# bromsbank.net
KiCad netlist of a schematic drawn in EAGLE
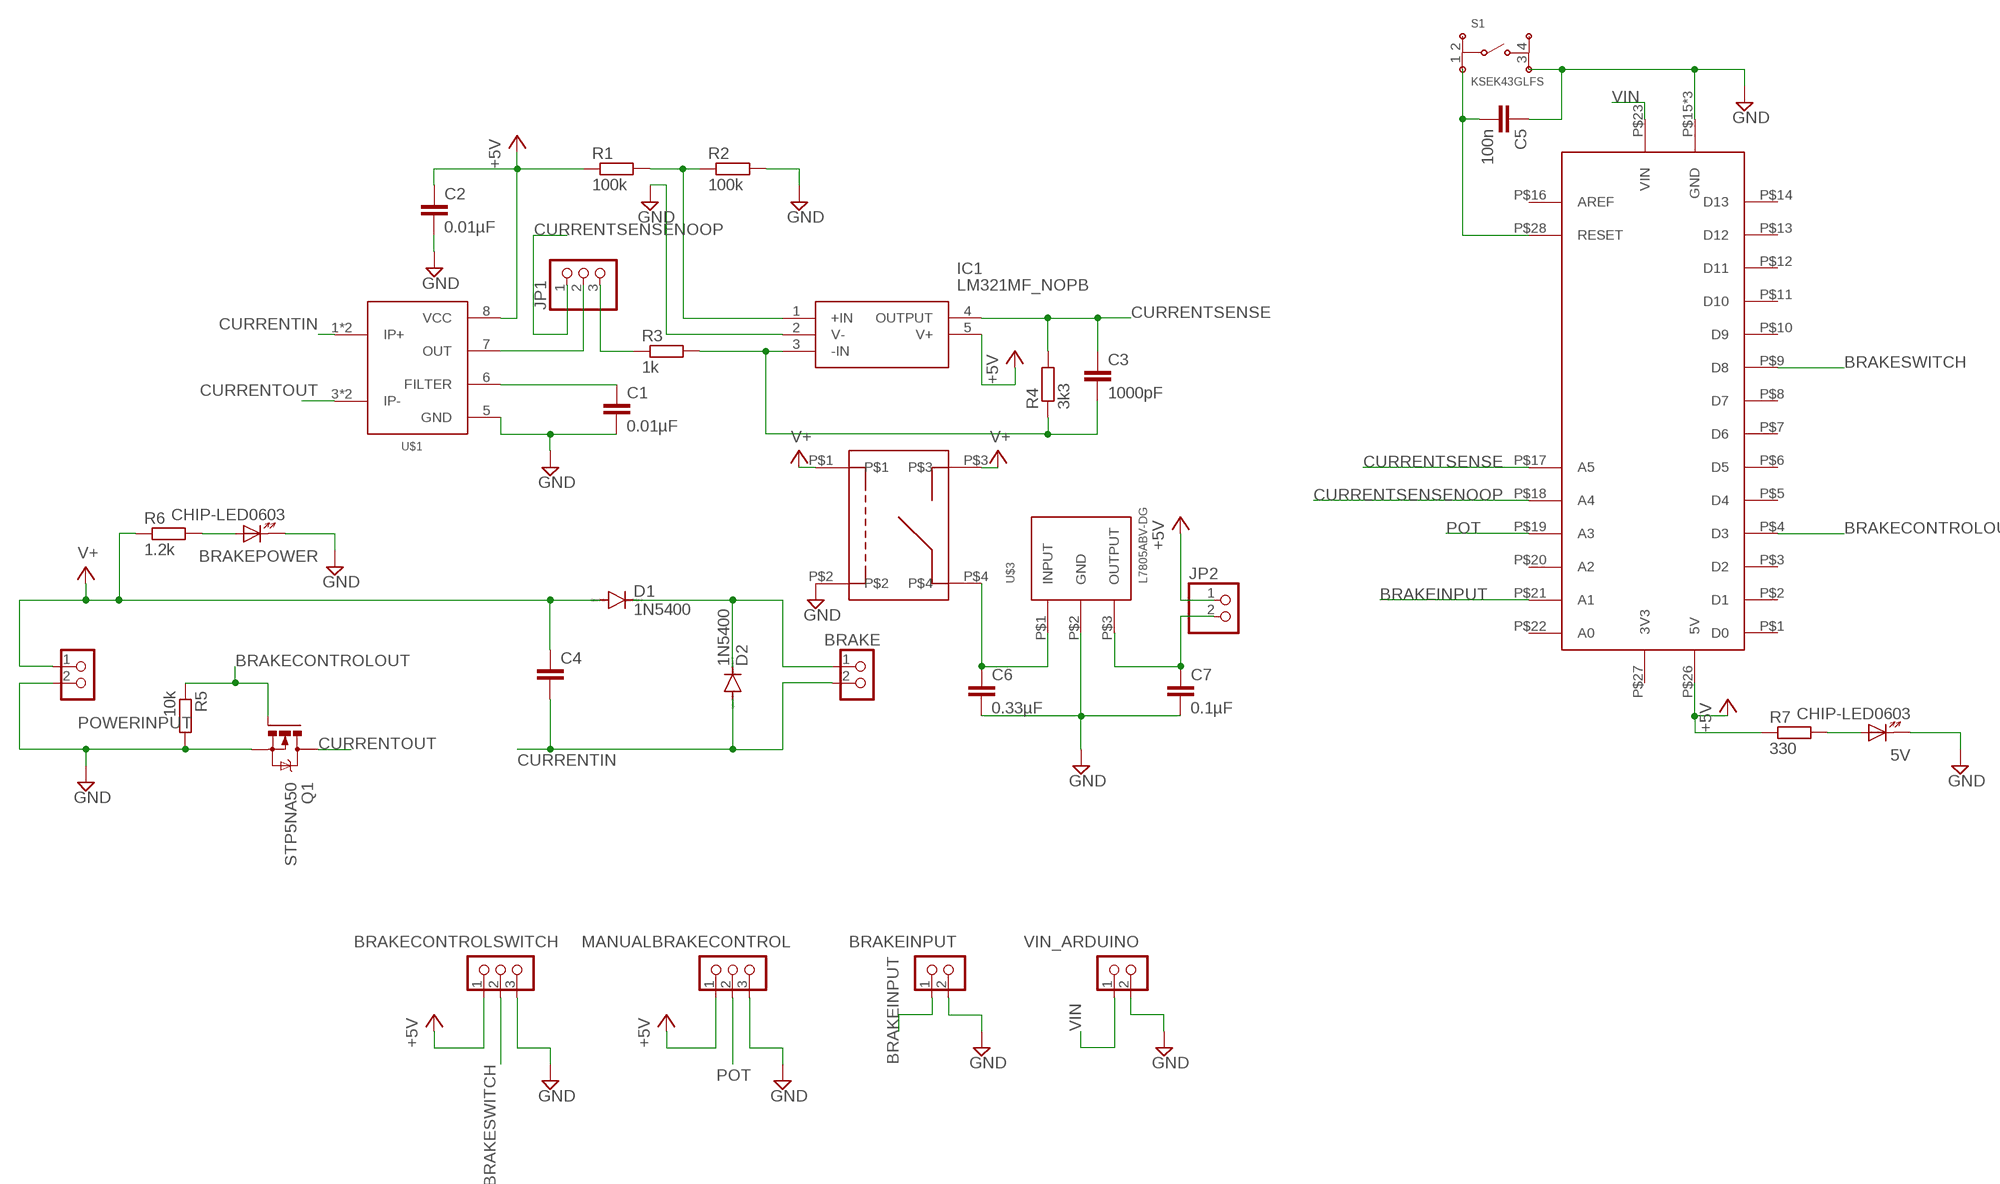
[diagram p0: schematic, sheet 1]

(export (version "E")
  (design (tool "Eeschema 10.0.6"))
  (components
    (comp (ref "5V")
      (value "CHIP-LED0603")
      (footprint "eagle-import:CHIP-LED0603")
      (libsource (lib "eagle-import") (part "CHIP-LED0603"))
    )
    (comp (ref "BRAKE")
      (value "EH_B2B-EH")
      (footprint "eagle-import:B2B-EH")
      (libsource (lib "eagle-import") (part "EH_B2B-EH"))
    )
    (comp (ref "BRAKECONTROLSWITCH")
      (value "EH_B3B-EH")
      (footprint "eagle-import:B3B-EH")
      (libsource (lib "eagle-import") (part "EH_B3B-EH"))
    )
    (comp (ref "BRAKEINPUT")
      (value "EH_B2B-EH")
      (footprint "eagle-import:B2B-EH")
      (libsource (lib "eagle-import") (part "EH_B2B-EH"))
    )
    (comp (ref "BRAKEPOWER")
      (value "CHIP-LED0603")
      (footprint "eagle-import:CHIP-LED0603")
      (libsource (lib "eagle-import") (part "CHIP-LED0603"))
    )
    (comp (ref "C1")
      (value "0.01µF")
      (footprint "eagle-import:C0603")
      (fields (field (name "SPICEPREFIX") "C"))
      (libsource (lib "eagle-import") (part "C0603"))
    )
    (comp (ref "C2")
      (value "0.01µF")
      (footprint "eagle-import:C0603")
      (libsource (lib "eagle-import") (part "C0603"))
    )
    (comp (ref "C3")
      (value "1000pF")
      (footprint "eagle-import:C0603")
      (libsource (lib "eagle-import") (part "C0603"))
    )
    (comp (ref "C4")
      (value "C-EU075-063X106")
      (footprint "eagle-import:C075-063X106")
      (libsource (lib "eagle-import") (part "C-EU075-063X106"))
    )
    (comp (ref "C5")
      (value "100n")
      (footprint "eagle-import:C0603")
      (libsource (lib "eagle-import") (part "C0603"))
    )
    (comp (ref "C6")
      (value "0.33µF")
      (footprint "eagle-import:C0603")
      (fields (field (name "SPICEPREFIX") "C"))
      (libsource (lib "eagle-import") (part "C0603"))
    )
    (comp (ref "C7")
      (value "0.1µF")
      (footprint "eagle-import:C0603")
      (fields (field (name "SPICEPREFIX") "C"))
      (libsource (lib "eagle-import") (part "C0603"))
    )
    (comp (ref "D1")
      (value "1N5400")
      (footprint "eagle-import:DO201-15")
      (libsource (lib "eagle-import") (part "1N5400"))
    )
    (comp (ref "D2")
      (value "1N5400")
      (footprint "eagle-import:DO201-15")
      (libsource (lib "eagle-import") (part "1N5400"))
    )
    (comp (ref "IC1")
      (value "LM321MF_NOPB")
      (footprint "eagle-import:SOT95P280X145-5N")
      (fields
        (field (name "MANUFACTURER_PART_NUMBER") "LM321MF/NOPB")
        (field (name "MOUSER_PART_NUMBER") "926-LM321MF/NOPB")
      )
      (libsource (lib "eagle-import") (part "LM321MF_NOPB"))
    )
    (comp (ref "JP1")
      (value "PINHD-1X3")
      (footprint "eagle-import:1X03")
      (libsource (lib "eagle-import") (part "PINHD-1X3"))
    )
    (comp (ref "JP2")
      (value "PINHD-1X2")
      (footprint "eagle-import:1X02")
      (libsource (lib "eagle-import") (part "PINHD-1X2"))
    )
    (comp (ref "MANUALBRAKECONTROL")
      (value "EH_B3B-EH")
      (footprint "eagle-import:B3B-EH")
      (libsource (lib "eagle-import") (part "EH_B3B-EH"))
    )
    (comp (ref "POWERINPUT")
      (value "EH_B2B-EH")
      (footprint "eagle-import:B2B-EH")
      (libsource (lib "eagle-import") (part "EH_B2B-EH"))
    )
    (comp (ref "Q1")
      (value "STP5NA50")
      (footprint "eagle-import:TO220BV")
      (libsource (lib "eagle-import") (part "STP5NA50"))
    )
    (comp (ref "R1")
      (value "100k")
      (footprint "eagle-import:R0603")
      (libsource (lib "eagle-import") (part "R0603"))
    )
    (comp (ref "R2")
      (value "100k")
      (footprint "eagle-import:R0603")
      (libsource (lib "eagle-import") (part "R0603"))
    )
    (comp (ref "R3")
      (value "1k")
      (footprint "eagle-import:R0603")
      (libsource (lib "eagle-import") (part "R0603"))
    )
    (comp (ref "R4")
      (value "3k3")
      (footprint "eagle-import:R0603")
      (libsource (lib "eagle-import") (part "R0603"))
    )
    (comp (ref "R5")
      (value "10k")
      (footprint "eagle-import:R0603")
      (libsource (lib "eagle-import") (part "R0603"))
    )
    (comp (ref "R6")
      (value "1.2k")
      (footprint "eagle-import:R0603")
      (libsource (lib "eagle-import") (part "R0603"))
    )
    (comp (ref "R7")
      (value "330")
      (footprint "eagle-import:R0603")
      (libsource (lib "eagle-import") (part "R0603"))
    )
    (comp (ref "S1")
      (value "KSEK43GLFS")
      (footprint "eagle-import:KSEK43GLFS")
      (libsource (lib "eagle-import") (part "KSEK43GLFS"))
    )
    (comp (ref "U$1")
      (value "ACS712ELCTR-05B-T")
      (footprint "eagle-import:SO08")
      (libsource (lib "eagle-import") (part "ACS712ELCTR-05B-T"))
    )
    (comp (ref "U$2")
      (value "ARDUINO_SHIELD")
      (footprint "eagle-import:ARDUINO_UNO_SHIELD")
      (libsource (lib "eagle-import") (part "ARDUINO_SHIELD"))
    )
    (comp (ref "U$3")
      (value "L7805ABV-DG")
      (footprint "eagle-import:TO-220")
      (libsource (lib "eagle-import") (part "L7805ABV-DG"))
    )
    (comp (ref "U$4")
      (value "RELAY_SDT-S-124DMR,601")
      (footprint "eagle-import:SDT-S-124DMR")
      (libsource (lib "eagle-import") (part "RELAY_SDT-S-124DMR,601"))
    )
    (comp (ref "VIN_ARDUINO")
      (value "EH_B2B-EH")
      (footprint "eagle-import:B2B-EH")
      (libsource (lib "eagle-import") (part "EH_B2B-EH"))
    )
  )
  (nets
    (net (code "1") (name "+5V") (class "Default")
      (node (ref "BRAKECONTROLSWITCH") (pin "1") (pinfunction "1_1") (pintype "passive"))
      (node (ref "C2") (pin "1") (pinfunction "1_1") (pintype "passive"))
      (node (ref "IC1") (pin "5") (pinfunction "V+_5") (pintype "bidirectional"))
      (node (ref "JP2") (pin "1") (pinfunction "1_1") (pintype "passive"))
      (node (ref "MANUALBRAKECONTROL") (pin "1") (pinfunction "1_1") (pintype "passive"))
      (node (ref "R1") (pin "1") (pinfunction "1_1") (pintype "passive"))
      (node (ref "R7") (pin "1") (pinfunction "1_1") (pintype "passive"))
      (node (ref "U$1") (pin "8") (pinfunction "VCC_8") (pintype "power_in"))
      (node (ref "U$2") (pin "P$26") (pinfunction "5V_P$26") (pintype "power_in"))
    )
    (net (code "2") (name "/3V3") (class "Default")
      (node (ref "U$2") (pin "P$27") (pinfunction "3V3_P$27") (pintype "power_in"))
    )
    (net (code "3") (name "/BRAKECONTROLOUT") (class "Default")
      (node (ref "Q1") (pin "G") (pinfunction "G_G") (pintype "passive"))
      (node (ref "R5") (pin "1") (pinfunction "1_1") (pintype "passive"))
      (node (ref "U$2") (pin "P$4") (pinfunction "D3_P$4") (pintype "bidirectional"))
    )
    (net (code "4") (name "/BRAKEINPUT") (class "Default")
      (node (ref "BRAKEINPUT") (pin "1") (pinfunction "1_1") (pintype "passive"))
      (node (ref "U$2") (pin "P$21") (pinfunction "A1_P$21") (pintype "input"))
    )
    (net (code "5") (name "/BRAKESWITCH") (class "Default")
      (node (ref "BRAKECONTROLSWITCH") (pin "2") (pinfunction "2_2") (pintype "passive"))
      (node (ref "U$2") (pin "P$9") (pinfunction "D8_P$9") (pintype "bidirectional"))
    )
    (net (code "6") (name "/CURRENTIN") (class "Default")
      (node (ref "BRAKE") (pin "2") (pinfunction "2_2") (pintype "passive"))
      (node (ref "C4") (pin "2") (pinfunction "2_2") (pintype "passive"))
      (node (ref "D2") (pin "A") (pinfunction "A_A") (pintype "passive"))
      (node (ref "U$1") (pin "1") (pinfunction "IP+_1") (pintype "bidirectional"))
      (node (ref "U$1") (pin "2") (pinfunction "IP+_2") (pintype "bidirectional"))
    )
    (net (code "7") (name "/CURRENTOUT") (class "Default")
      (node (ref "Q1") (pin "D") (pinfunction "D_D") (pintype "passive"))
      (node (ref "U$1") (pin "3") (pinfunction "IP-_3") (pintype "bidirectional"))
      (node (ref "U$1") (pin "4") (pinfunction "IP-_4") (pintype "bidirectional"))
    )
    (net (code "8") (name "/CURRENTSENSE") (class "Default")
      (node (ref "C3") (pin "1") (pinfunction "1_1") (pintype "passive"))
      (node (ref "IC1") (pin "4") (pinfunction "OUTPUT_4") (pintype "bidirectional"))
      (node (ref "R4") (pin "2") (pinfunction "2_2") (pintype "passive"))
      (node (ref "U$2") (pin "P$17") (pinfunction "A5_P$17") (pintype "input"))
    )
    (net (code "9") (name "/CURRENTSENSENOOP") (class "Default")
      (node (ref "JP1") (pin "1") (pinfunction "1_1") (pintype "passive"))
      (node (ref "U$2") (pin "P$18") (pinfunction "A4_P$18") (pintype "input"))
    )
    (net (code "10") (name "/POT") (class "Default")
      (node (ref "MANUALBRAKECONTROL") (pin "2") (pinfunction "2_2") (pintype "passive"))
      (node (ref "U$2") (pin "P$19") (pinfunction "A3_P$19") (pintype "input"))
    )
    (net (code "11") (name "/VIN") (class "Default")
      (node (ref "U$2") (pin "P$23") (pinfunction "VIN_P$23") (pintype "power_in"))
      (node (ref "VIN_ARDUINO") (pin "1") (pinfunction "1_1") (pintype "passive"))
    )
    (net (code "12") (name "GND") (class "Default")
      (node (ref "5V") (pin "C") (pinfunction "K_C") (pintype "passive"))
      (node (ref "BRAKECONTROLSWITCH") (pin "3") (pinfunction "3_3") (pintype "passive"))
      (node (ref "BRAKEINPUT") (pin "2") (pinfunction "2_2") (pintype "passive"))
      (node (ref "BRAKEPOWER") (pin "C") (pinfunction "K_C") (pintype "passive"))
      (node (ref "C1") (pin "2") (pinfunction "2_2") (pintype "passive"))
      (node (ref "C2") (pin "2") (pinfunction "2_2") (pintype "passive"))
      (node (ref "C5") (pin "1") (pinfunction "1_1") (pintype "passive"))
      (node (ref "C6") (pin "2") (pinfunction "2_2") (pintype "passive"))
      (node (ref "C7") (pin "2") (pinfunction "2_2") (pintype "passive"))
      (node (ref "IC1") (pin "2") (pinfunction "V-_2") (pintype "bidirectional"))
      (node (ref "MANUALBRAKECONTROL") (pin "3") (pinfunction "3_3") (pintype "passive"))
      (node (ref "POWERINPUT") (pin "2") (pinfunction "2_2") (pintype "passive"))
      (node (ref "Q1") (pin "S") (pinfunction "S_S") (pintype "passive"))
      (node (ref "R2") (pin "2") (pinfunction "2_2") (pintype "passive"))
      (node (ref "R5") (pin "2") (pinfunction "2_2") (pintype "passive"))
      (node (ref "S1") (pin "3") (pinfunction "3_3") (pintype "bidirectional"))
      (node (ref "U$1") (pin "5") (pinfunction "GND_5") (pintype "power_in"))
      (node (ref "U$2") (pin "P$15") (pinfunction "GND_P$15") (pintype "power_in"))
      (node (ref "U$2") (pin "P$24") (pinfunction "GND_P$24") (pintype "power_in"))
      (node (ref "U$2") (pin "P$25") (pinfunction "GND_P$25") (pintype "power_in"))
      (node (ref "U$3") (pin "P$2") (pinfunction "GND_P$2") (pintype "power_in"))
      (node (ref "U$4") (pin "P$2") (pinfunction "P$2_P$2") (pintype "bidirectional"))
      (node (ref "VIN_ARDUINO") (pin "2") (pinfunction "2_2") (pintype "passive"))
    )
    (net (code "13") (name "Net-(5V-PadA)") (class "Default")
      (node (ref "5V") (pin "A") (pinfunction "A_A") (pintype "passive"))
      (node (ref "R7") (pin "2") (pinfunction "2_2") (pintype "passive"))
    )
    (net (code "14") (name "Net-(BRAKE-Pad1)") (class "Default")
      (node (ref "BRAKE") (pin "1") (pinfunction "1_1") (pintype "passive"))
      (node (ref "D1") (pin "C") (pinfunction "C_C") (pintype "passive"))
      (node (ref "D2") (pin "C") (pinfunction "C_C") (pintype "passive"))
    )
    (net (code "15") (name "Net-(BRAKEPOWER-PadA)") (class "Default")
      (node (ref "BRAKEPOWER") (pin "A") (pinfunction "A_A") (pintype "passive"))
      (node (ref "R6") (pin "2") (pinfunction "2_2") (pintype "passive"))
    )
    (net (code "16") (name "Net-(IC1-+IN)") (class "Default")
      (node (ref "IC1") (pin "1") (pinfunction "+IN_1") (pintype "bidirectional"))
      (node (ref "R1") (pin "2") (pinfunction "2_2") (pintype "passive"))
      (node (ref "R2") (pin "1") (pinfunction "1_1") (pintype "passive"))
    )
    (net (code "17") (name "Net-(IC1--IN)") (class "Default")
      (node (ref "C3") (pin "2") (pinfunction "2_2") (pintype "passive"))
      (node (ref "IC1") (pin "3") (pinfunction "-IN_3") (pintype "bidirectional"))
      (node (ref "R3") (pin "2") (pinfunction "2_2") (pintype "passive"))
      (node (ref "R4") (pin "1") (pinfunction "1_1") (pintype "passive"))
    )
    (net (code "18") (name "Net-(JP1-Pad3)") (class "Default")
      (node (ref "JP1") (pin "3") (pinfunction "3_3") (pintype "passive"))
      (node (ref "R3") (pin "1") (pinfunction "1_1") (pintype "passive"))
    )
    (net (code "19") (name "Net-(U$1-FILTER)") (class "Default")
      (node (ref "C1") (pin "1") (pinfunction "1_1") (pintype "passive"))
      (node (ref "U$1") (pin "6") (pinfunction "FILTER_6") (pintype "power_in"))
    )
    (net (code "20") (name "Net-(U$1-OUT)") (class "Default")
      (node (ref "JP1") (pin "2") (pinfunction "2_2") (pintype "passive"))
      (node (ref "U$1") (pin "7") (pinfunction "OUT_7") (pintype "output"))
    )
    (net (code "21") (name "Net-(U$2-RESET)") (class "Default")
      (node (ref "C5") (pin "2") (pinfunction "2_2") (pintype "passive"))
      (node (ref "S1") (pin "1") (pinfunction "1_1") (pintype "bidirectional"))
      (node (ref "U$2") (pin "P$28") (pinfunction "RESET_P$28") (pintype "input"))
    )
    (net (code "22") (name "Net-(U$3-INPUT)") (class "Default")
      (node (ref "C6") (pin "1") (pinfunction "1_1") (pintype "passive"))
      (node (ref "U$3") (pin "P$1") (pinfunction "INPUT_P$1") (pintype "power_in"))
      (node (ref "U$4") (pin "P$4") (pinfunction "P$4_P$4") (pintype "power_in"))
    )
    (net (code "23") (name "Net-(U$3-OUTPUT)") (class "Default")
      (node (ref "C7") (pin "1") (pinfunction "1_1") (pintype "passive"))
      (node (ref "JP2") (pin "2") (pinfunction "2_2") (pintype "passive"))
      (node (ref "U$3") (pin "P$3") (pinfunction "OUTPUT_P$3") (pintype "power_in"))
    )
    (net (code "24") (name "V+") (class "Default")
      (node (ref "C4") (pin "1") (pinfunction "1_1") (pintype "passive"))
      (node (ref "D1") (pin "A") (pinfunction "A_A") (pintype "passive"))
      (node (ref "POWERINPUT") (pin "1") (pinfunction "1_1") (pintype "passive"))
      (node (ref "R6") (pin "1") (pinfunction "1_1") (pintype "passive"))
      (node (ref "U$4") (pin "P$1") (pinfunction "P$1_P$1") (pintype "bidirectional"))
      (node (ref "U$4") (pin "P$3") (pinfunction "P$3_P$3") (pintype "power_in"))
    )
    (net (code "25") (name "unconnected-(S1-Pad2)") (class "Default")
      (node (ref "S1") (pin "2") (pinfunction "2_2") (pintype "bidirectional"))
    )
    (net (code "26") (name "unconnected-(S1-Pad4)") (class "Default")
      (node (ref "S1") (pin "4") (pinfunction "4_4") (pintype "bidirectional"))
    )
    (net (code "27") (name "unconnected-(U$2-A0-PadP$22)") (class "Default")
      (node (ref "U$2") (pin "P$22") (pinfunction "A0_P$22") (pintype "input"))
    )
    (net (code "28") (name "unconnected-(U$2-A2-PadP$20)") (class "Default")
      (node (ref "U$2") (pin "P$20") (pinfunction "A2_P$20") (pintype "input"))
    )
    (net (code "29") (name "unconnected-(U$2-AREF-PadP$16)") (class "Default")
      (node (ref "U$2") (pin "P$16") (pinfunction "AREF_P$16") (pintype "input"))
    )
    (net (code "30") (name "unconnected-(U$2-D0-PadP$1)") (class "Default")
      (node (ref "U$2") (pin "P$1") (pinfunction "D0_P$1") (pintype "bidirectional"))
    )
    (net (code "31") (name "unconnected-(U$2-D1-PadP$2)") (class "Default")
      (node (ref "U$2") (pin "P$2") (pinfunction "D1_P$2") (pintype "bidirectional"))
    )
    (net (code "32") (name "unconnected-(U$2-D2-PadP$3)") (class "Default")
      (node (ref "U$2") (pin "P$3") (pinfunction "D2_P$3") (pintype "bidirectional"))
    )
    (net (code "33") (name "unconnected-(U$2-D4-PadP$5)") (class "Default")
      (node (ref "U$2") (pin "P$5") (pinfunction "D4_P$5") (pintype "bidirectional"))
    )
    (net (code "34") (name "unconnected-(U$2-D5-PadP$6)") (class "Default")
      (node (ref "U$2") (pin "P$6") (pinfunction "D5_P$6") (pintype "bidirectional"))
    )
    (net (code "35") (name "unconnected-(U$2-D6-PadP$7)") (class "Default")
      (node (ref "U$2") (pin "P$7") (pinfunction "D6_P$7") (pintype "bidirectional"))
    )
    (net (code "36") (name "unconnected-(U$2-D7-PadP$8)") (class "Default")
      (node (ref "U$2") (pin "P$8") (pinfunction "D7_P$8") (pintype "bidirectional"))
    )
    (net (code "37") (name "unconnected-(U$2-D9-PadP$10)") (class "Default")
      (node (ref "U$2") (pin "P$10") (pinfunction "D9_P$10") (pintype "bidirectional"))
    )
    (net (code "38") (name "unconnected-(U$2-D10-PadP$11)") (class "Default")
      (node (ref "U$2") (pin "P$11") (pinfunction "D10_P$11") (pintype "bidirectional"))
    )
    (net (code "39") (name "unconnected-(U$2-D11-PadP$12)") (class "Default")
      (node (ref "U$2") (pin "P$12") (pinfunction "D11_P$12") (pintype "bidirectional"))
    )
    (net (code "40") (name "unconnected-(U$2-D12-PadP$13)") (class "Default")
      (node (ref "U$2") (pin "P$13") (pinfunction "D12_P$13") (pintype "bidirectional"))
    )
    (net (code "41") (name "unconnected-(U$2-D13-PadP$14)") (class "Default")
      (node (ref "U$2") (pin "P$14") (pinfunction "D13_P$14") (pintype "bidirectional"))
    )
  )
)
